# main.net
KiCad netlist of a schematic drawn in Altium Designer
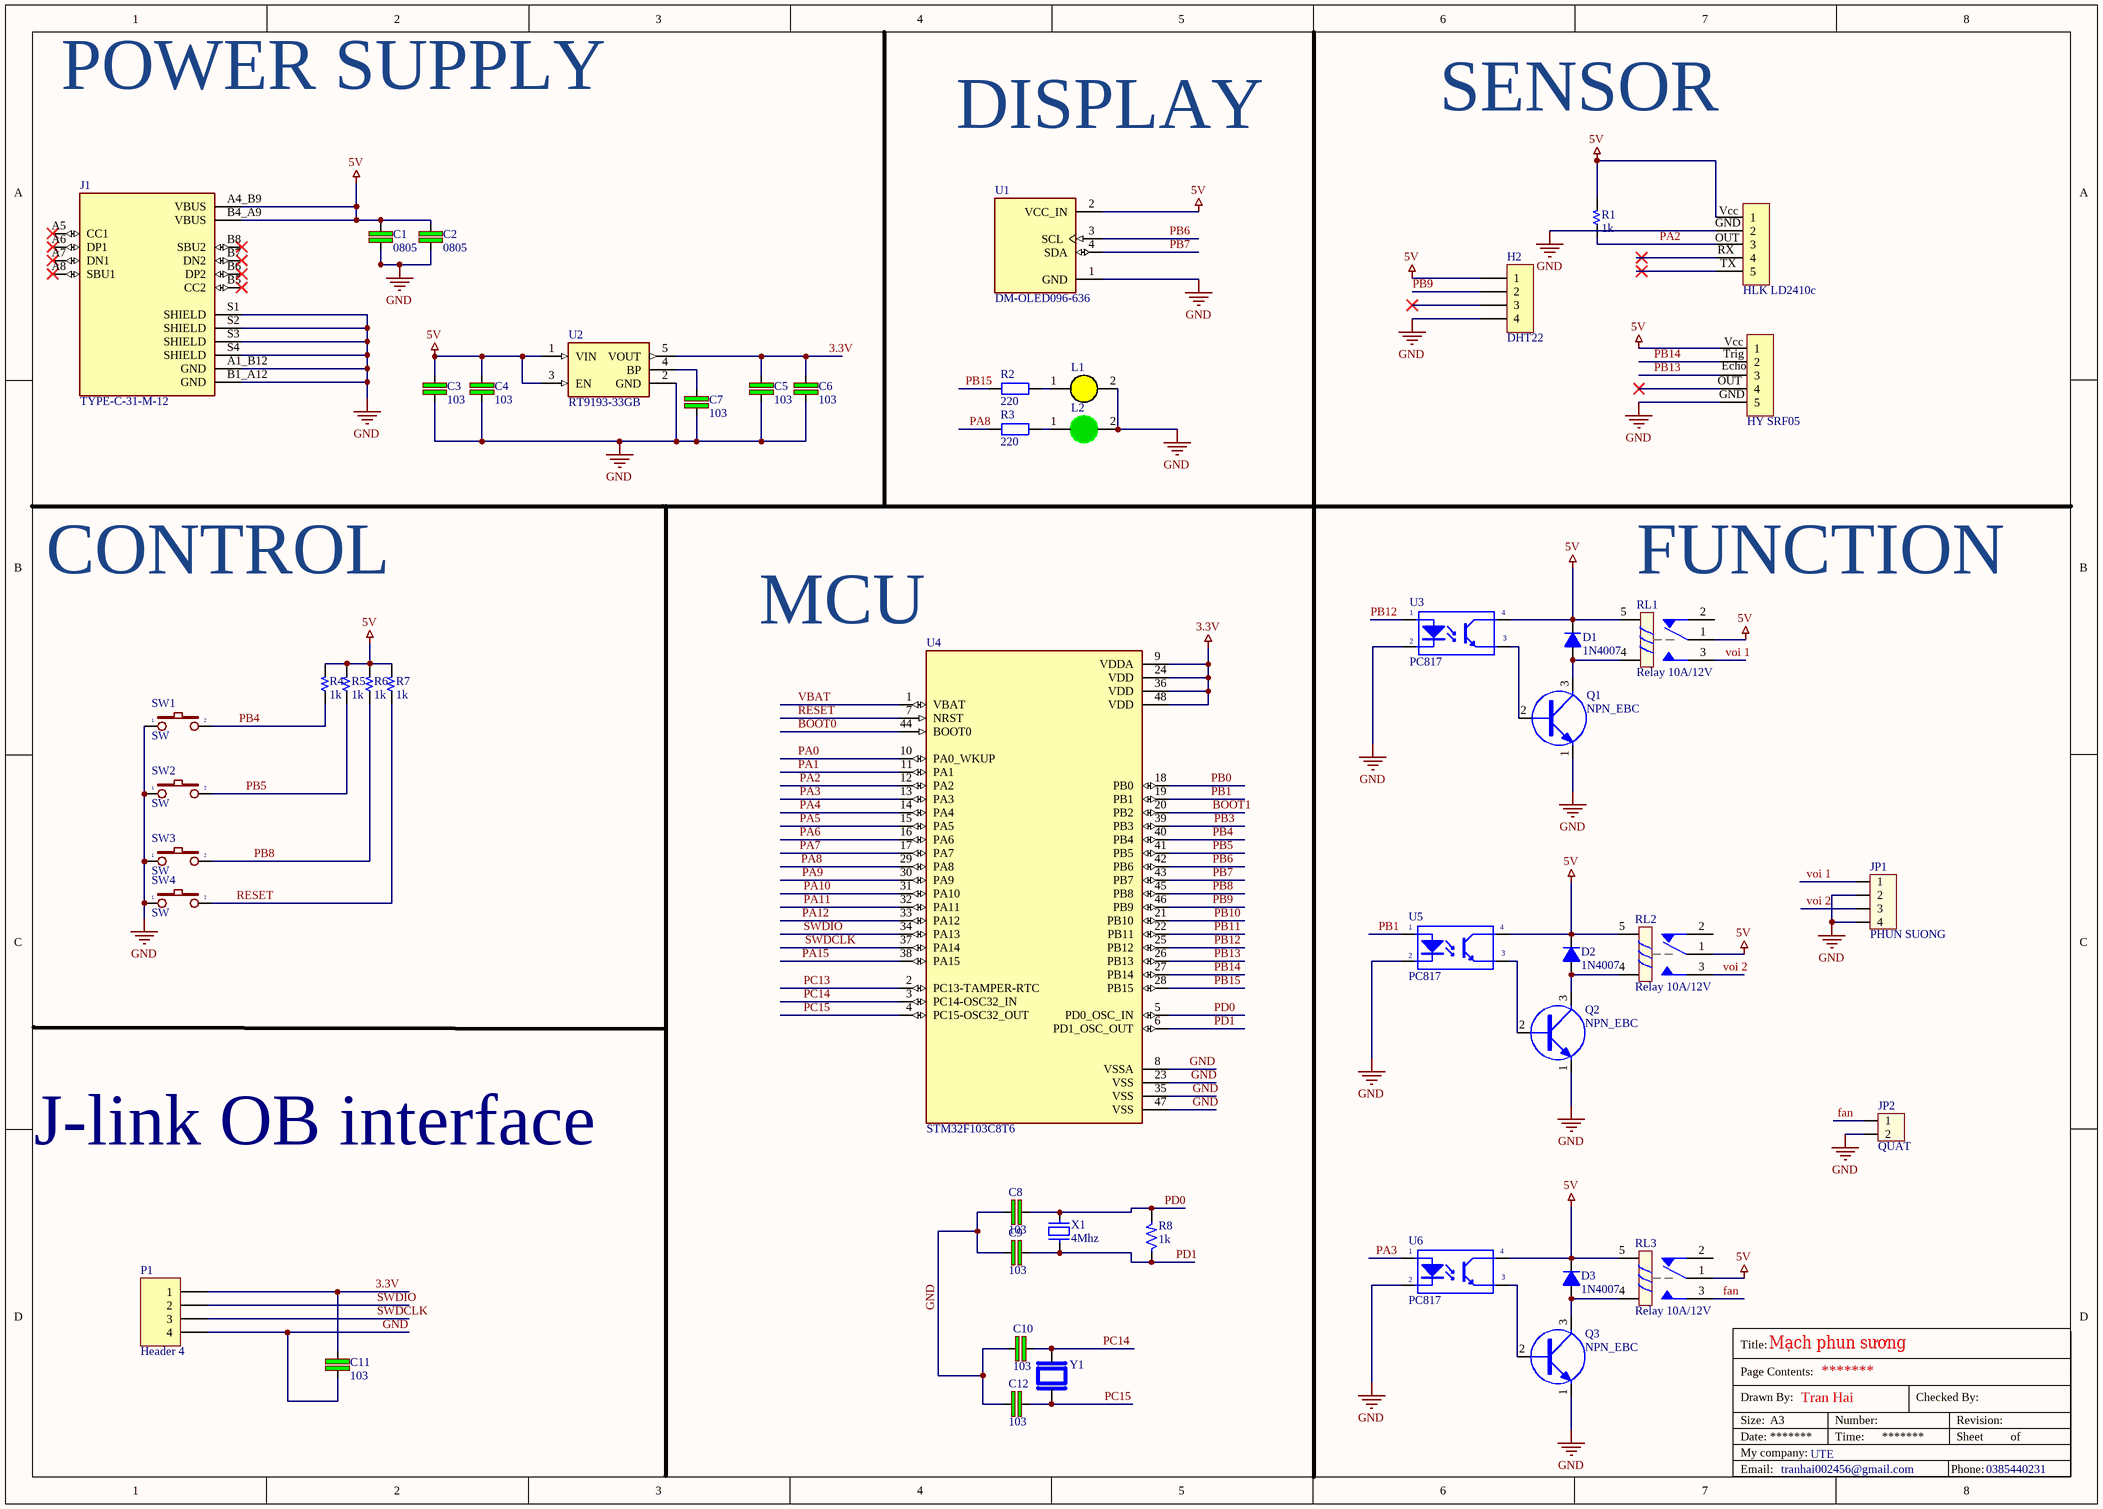
[diagram p0: main.SchDoc]

(export (version "E")
  (design (tool "Eeschema 10.0.6"))
  (components
    (comp (ref "C1")
      (value "0805")
      (footprint "C-0805")
      (description "Cap SMD")
      (libsource (lib "Library AL") (part "C"))
    )
    (comp (ref "C2")
      (value "0805")
      (footprint "C-0805")
      (description "Cap SMD")
      (libsource (lib "Library AL") (part "C"))
    )
    (comp (ref "C3")
      (value "103")
      (footprint "C-0805")
      (description "Cap SMD")
      (libsource (lib "Library AL") (part "C"))
    )
    (comp (ref "C4")
      (value "103")
      (footprint "C-0805")
      (description "Cap SMD")
      (libsource (lib "Library AL") (part "C"))
    )
    (comp (ref "C5")
      (value "103")
      (footprint "C-0805")
      (description "Cap SMD")
      (libsource (lib "Library AL") (part "C"))
    )
    (comp (ref "C6")
      (value "103")
      (footprint "C-0805")
      (description "Cap SMD")
      (libsource (lib "Library AL") (part "C"))
    )
    (comp (ref "C7")
      (value "103")
      (footprint "C-0805")
      (description "Cap SMD")
      (libsource (lib "Library AL") (part "C"))
    )
    (comp (ref "C8")
      (value "103")
      (footprint "C-0805")
      (description "Cap SMD")
      (libsource (lib "") (part "C_1"))
    )
    (comp (ref "C9")
      (value "103")
      (footprint "C-0805")
      (description "Cap SMD")
      (libsource (lib "") (part "C_1"))
    )
    (comp (ref "C10")
      (value "103")
      (footprint "C-0805")
      (description "Cap SMD")
      (libsource (lib "") (part "C_1"))
    )
    (comp (ref "C11")
      (value "103")
      (footprint "C-0805")
      (description "Cap SMD")
      (libsource (lib "Library AL") (part "C"))
    )
    (comp (ref "C12")
      (value "103")
      (footprint "C-0805")
      (description "Cap SMD")
      (libsource (lib "") (part "C_1"))
    )
    (comp (ref "D1")
      (value "1N4007")
      (footprint "D1A")
      (description "Diode 1A")
      (libsource (lib "Library AL") (part "D1A"))
    )
    (comp (ref "D2")
      (value "1N4007")
      (footprint "D1A")
      (description "Diode 1A")
      (libsource (lib "Library AL") (part "D1A"))
    )
    (comp (ref "D3")
      (value "1N4007")
      (footprint "D1A")
      (description "Diode 1A")
      (libsource (lib "Library AL") (part "D1A"))
    )
    (comp (ref "H1")
      (value "HLK LD2410c")
      (footprint "Header 5P DC 2.54")
      (description "Cắm")
      (libsource (lib "Altium_Lib_by_KhueNguyenCreator") (part "Header 5P 2.54 Duc Cong"))
    )
    (comp (ref "H2")
      (value "DHT22")
      (footprint "XH2.54M-4")
      (description "Cắm")
      (libsource (lib "Altium_Lib_by_KhueNguyenCreator") (part "Header 4P 2.54 Duc Thang"))
    )
    (comp (ref "H3")
      (value "HY SRF05")
      (footprint "XH2.54M-5")
      (description "Cắm")
      (libsource (lib "Altium_Lib_by_KhueNguyenCreator") (part "Header 5P 2.54 Duc Thang"))
    )
    (comp (ref "J1")
      (value "TYPE-C-31-M-12")
      (footprint "HRO_TYPE-C-31-M-12")
      (description "USB Connectors 24 Receptacle 1 8.94*7.3mm RoHS")
      (fields (field (name "MF") "HRO Electronics Co., Ltd."))
      (libsource (lib "TYPE-C-31-M-12") (part "TYPE-C-31-M-12"))
    )
    (comp (ref "JP1")
      (value "PHUN SUONG")
      (footprint "CON4")
      (description "Connector 4")
      (libsource (lib "Library AL") (part "Con4"))
    )
    (comp (ref "JP2")
      (value "QUAT")
      (footprint "CON2")
      (description "Connector 2")
      (libsource (lib "Library AL") (part "Con2"))
    )
    (comp (ref "L1")
      (value "LED 0805")
      (footprint "LED-0805-Yellow")
      (description "Dán")
      (libsource (lib "Altium_Lib_by_KhueNguyenCreator") (part "LED 0805 Vang"))
    )
    (comp (ref "L2")
      (value "LED 0805")
      (footprint "LED-0805-Green")
      (description "Dán")
      (libsource (lib "Altium_Lib_by_KhueNguyenCreator") (part "LED 0805 Xanh La"))
    )
    (comp (ref "P1")
      (value "Header 4")
      (footprint "HDR1X4")
      (description "Header, 4-Pin")
      (fields (field (name "PUBLISHER") "Altium Limited"))
      (libsource (lib "Library AL") (part "Header 4"))
    )
    (comp (ref "Q1")
      (value "NPN_EBC")
      (footprint "QTO-92")
      (description "NPN Transistor")
      (libsource (lib "Library AL") (part "NPN_EBC"))
    )
    (comp (ref "Q2")
      (value "NPN_EBC")
      (footprint "QTO-92")
      (description "NPN Transistor")
      (libsource (lib "Library AL") (part "NPN_EBC"))
    )
    (comp (ref "Q3")
      (value "NPN_EBC")
      (footprint "QTO-92")
      (description "NPN Transistor")
      (libsource (lib "Library AL") (part "NPN_EBC"))
    )
    (comp (ref "R1")
      (value "1k")
      (footprint "TRO SMD 0603")
      (libsource (lib "Altium_Lib_by_KhueNguyenCreator") (part "Res_0603"))
    )
    (comp (ref "R2")
      (value "220")
      (footprint "tro smd 0603")
      (description "Dán")
      (libsource (lib "Altium_Lib_by_KhueNguyenCreator") (part "Tro 0603 1% 0R"))
    )
    (comp (ref "R3")
      (value "220")
      (footprint "tro smd 0603")
      (description "Dán")
      (libsource (lib "Altium_Lib_by_KhueNguyenCreator") (part "Tro 0603 1% 0R"))
    )
    (comp (ref "R4")
      (value "1k")
      (footprint "TRO SMD 0603")
      (libsource (lib "Altium_Lib_by_KhueNguyenCreator") (part "Res_0603"))
    )
    (comp (ref "R5")
      (value "1k")
      (footprint "TRO SMD 0603")
      (libsource (lib "Altium_Lib_by_KhueNguyenCreator") (part "Res_0603"))
    )
    (comp (ref "R6")
      (value "1k")
      (footprint "TRO SMD 0603")
      (libsource (lib "Altium_Lib_by_KhueNguyenCreator") (part "Res_0603"))
    )
    (comp (ref "R7")
      (value "1k")
      (footprint "TRO SMD 0603")
      (libsource (lib "Altium_Lib_by_KhueNguyenCreator") (part "Res_0603"))
    )
    (comp (ref "R8")
      (value "1k")
      (footprint "SM-1206")
      (description "Resistor 1/4W")
      (libsource (lib "Library AL") (part "R"))
    )
    (comp (ref "RL1")
      (value "Relay 10A/12V")
      (footprint "RL_SPDT_10A")
      (description "Relay SPDT,10A - 12VDC 5 Pin")
      (libsource (lib "syhaunguyen") (part "Relay 1"))
    )
    (comp (ref "RL2")
      (value "Relay 10A/12V")
      (footprint "RL_SPDT_10A")
      (description "Relay SPDT,10A - 12VDC 5 Pin")
      (libsource (lib "syhaunguyen") (part "Relay 1"))
    )
    (comp (ref "RL3")
      (value "Relay 10A/12V")
      (footprint "RL_SPDT_10A")
      (description "Relay SPDT,10A - 12VDC 5 Pin")
      (libsource (lib "syhaunguyen") (part "Relay 1"))
    )
    (comp (ref "SW1")
      (value "SW")
      (footprint "SW2")
      (description "Switch button 2 pin")
      (libsource (lib "Library AL") (part "SW2"))
    )
    (comp (ref "SW2")
      (value "SW")
      (footprint "SW2")
      (description "Switch button 2 pin")
      (libsource (lib "Library AL") (part "SW2"))
    )
    (comp (ref "SW3")
      (value "SW")
      (footprint "SW2")
      (description "Switch button 2 pin")
      (libsource (lib "Library AL") (part "SW2"))
    )
    (comp (ref "SW4")
      (value "SW")
      (footprint "SW2")
      (description "Switch button 2 pin")
      (libsource (lib "Library AL") (part "SW2"))
    )
    (comp (ref "U1")
      (value "DM-OLED096-636")
      (footprint "MODULE_DM-OLED096-636")
      (description "0.96â€ 128 X 64 MONOCHROME GRAPHIC OLED DISPLAY MODULE - I2C")
      (fields (field (name "MF") "Display Module"))
      (libsource (lib "DM-OLED096-636") (part "DM-OLED096-636"))
    )
    (comp (ref "U2")
      (value "RT9193-33GB")
      (footprint "SOT94P279X129-5N")
      (description "Linear Voltage Regulator IC Positive Fixed 1 Output 300mA TSOT-23-5")
      (fields (field (name "MF") "Richtek USA") (field (name "DIGI-KEY_PART_NUMBER") "1028-1014-2-ND"))
      (libsource (lib "RT9193-33GB") (part "RT9193-33GB"))
    )
    (comp (ref "U3")
      (value "PC817")
      (footprint "DIP4/W0.3")
      (description "Single Opto")
      (libsource (lib "syhaunguyen") (part "PC817"))
    )
    (comp (ref "U4")
      (value "STM32F103C8T6")
      (footprint "QFP50P900X900X160-48N")
      (description "ARM® Cortex®-M3 STM32F1 Microcontroller IC 32-Bit 72MHz 64KB (64K x 8) FLASH 48-LQFP (7x7)")
      (fields (field (name "MF") "STMicroelectronics"))
      (libsource (lib "STM32F103C8T6") (part "STM32F103C8T6"))
    )
    (comp (ref "U5")
      (value "PC817")
      (footprint "DIP4/W0.3")
      (description "Single Opto")
      (libsource (lib "syhaunguyen") (part "PC817"))
    )
    (comp (ref "U6")
      (value "PC817")
      (footprint "DIP4/W0.3")
      (description "Single Opto")
      (libsource (lib "syhaunguyen") (part "PC817"))
    )
    (comp (ref "X1")
      (value "4Mhz")
      (footprint "XT2")
      (description "Crystal For all Crystal 2pin.")
      (libsource (lib "syhaunguyen") (part "XT2"))
    )
    (comp (ref "Y1")
      (value "ABS07-32.768KHZ-T")
      (footprint "XTAL_ABS07-32.768KHZ-T")
      (description "32.768 kHz Â±20ppm Crystal 12.5pF 70 kOhms 2-SMD, No Lead")
      (fields (field (name "MF") "Abracon"))
      (libsource (lib "ABS07-32.768KHZ-T") (part "ABS07-32.768KHZ-T"))
    )
  )
  (nets
    (net (code "1") (name "/BOOT0") (class "Default")
      (node (ref "U4") (pin "44") (pinfunction "BOOT0_44") (pintype "input"))
    )
    (net (code "2") (name "/BOOT1") (class "Default")
      (node (ref "U4") (pin "20") (pinfunction "PB2_20") (pintype "bidirectional"))
    )
    (net (code "3") (name "/PA0") (class "Default")
      (node (ref "U4") (pin "10") (pinfunction "PA0_WKUP_10") (pintype "bidirectional"))
    )
    (net (code "4") (name "/PA1") (class "Default")
      (node (ref "U4") (pin "11") (pinfunction "PA1_11") (pintype "bidirectional"))
    )
    (net (code "5") (name "/PA2") (class "Default")
      (node (ref "H1") (pin "3") (pinfunction "3_3") (pintype "passive"))
      (node (ref "R1") (pin "1") (pinfunction "1_1") (pintype "passive"))
      (node (ref "U4") (pin "12") (pinfunction "PA2_12") (pintype "bidirectional"))
    )
    (net (code "6") (name "/PA3") (class "Default")
      (node (ref "U4") (pin "13") (pinfunction "PA3_13") (pintype "bidirectional"))
      (node (ref "U6") (pin "1") (pinfunction "A_1") (pintype "passive"))
    )
    (net (code "7") (name "/PA4") (class "Default")
      (node (ref "U4") (pin "14") (pinfunction "PA4_14") (pintype "bidirectional"))
    )
    (net (code "8") (name "/PA5") (class "Default")
      (node (ref "U4") (pin "15") (pinfunction "PA5_15") (pintype "bidirectional"))
    )
    (net (code "9") (name "/PA6") (class "Default")
      (node (ref "U4") (pin "16") (pinfunction "PA6_16") (pintype "bidirectional"))
    )
    (net (code "10") (name "/PA7") (class "Default")
      (node (ref "U4") (pin "17") (pinfunction "PA7_17") (pintype "bidirectional"))
    )
    (net (code "11") (name "/PA8") (class "Default")
      (node (ref "R3") (pin "1") (pinfunction "1_1") (pintype "passive"))
      (node (ref "U4") (pin "29") (pinfunction "PA8_29") (pintype "bidirectional"))
    )
    (net (code "12") (name "/PA9") (class "Default")
      (node (ref "U4") (pin "30") (pinfunction "PA9_30") (pintype "bidirectional"))
    )
    (net (code "13") (name "/PA10") (class "Default")
      (node (ref "U4") (pin "31") (pinfunction "PA10_31") (pintype "bidirectional"))
    )
    (net (code "14") (name "/PA11") (class "Default")
      (node (ref "U4") (pin "32") (pinfunction "PA11_32") (pintype "bidirectional"))
    )
    (net (code "15") (name "/PA12") (class "Default")
      (node (ref "U4") (pin "33") (pinfunction "PA12_33") (pintype "bidirectional"))
    )
    (net (code "16") (name "/PA15") (class "Default")
      (node (ref "U4") (pin "38") (pinfunction "PA15_38") (pintype "bidirectional"))
    )
    (net (code "17") (name "/PB0") (class "Default")
      (node (ref "U4") (pin "18") (pinfunction "PB0_18") (pintype "bidirectional"))
    )
    (net (code "18") (name "/PB1") (class "Default")
      (node (ref "U4") (pin "19") (pinfunction "PB1_19") (pintype "bidirectional"))
      (node (ref "U5") (pin "1") (pinfunction "A_1") (pintype "passive"))
    )
    (net (code "19") (name "/PB3") (class "Default")
      (node (ref "U4") (pin "39") (pinfunction "PB3_39") (pintype "bidirectional"))
    )
    (net (code "20") (name "/PB4") (class "Default")
      (node (ref "R4") (pin "1") (pinfunction "1_1") (pintype "passive"))
      (node (ref "SW1") (pin "2") (pinfunction "2_2") (pintype "passive"))
      (node (ref "U4") (pin "40") (pinfunction "PB4_40") (pintype "bidirectional"))
    )
    (net (code "21") (name "/PB5") (class "Default")
      (node (ref "R5") (pin "1") (pinfunction "1_1") (pintype "passive"))
      (node (ref "SW2") (pin "2") (pinfunction "2_2") (pintype "passive"))
      (node (ref "U4") (pin "41") (pinfunction "PB5_41") (pintype "bidirectional"))
    )
    (net (code "22") (name "/PB6") (class "Default")
      (node (ref "U1") (pin "3") (pinfunction "SCL_3") (pintype "input"))
      (node (ref "U4") (pin "42") (pinfunction "PB6_42") (pintype "bidirectional"))
    )
    (net (code "23") (name "/PB7") (class "Default")
      (node (ref "U1") (pin "4") (pinfunction "SDA_4") (pintype "bidirectional"))
      (node (ref "U4") (pin "43") (pinfunction "PB7_43") (pintype "bidirectional"))
    )
    (net (code "24") (name "/PB8") (class "Default")
      (node (ref "R6") (pin "1") (pinfunction "1_1") (pintype "passive"))
      (node (ref "SW3") (pin "2") (pinfunction "2_2") (pintype "passive"))
      (node (ref "U4") (pin "45") (pinfunction "PB8_45") (pintype "bidirectional"))
    )
    (net (code "25") (name "/PB9") (class "Default")
      (node (ref "H2") (pin "2") (pinfunction "2_2") (pintype "passive"))
      (node (ref "U4") (pin "46") (pinfunction "PB9_46") (pintype "bidirectional"))
    )
    (net (code "26") (name "/PB10") (class "Default")
      (node (ref "U4") (pin "21") (pinfunction "PB10_21") (pintype "bidirectional"))
    )
    (net (code "27") (name "/PB11") (class "Default")
      (node (ref "U4") (pin "22") (pinfunction "PB11_22") (pintype "bidirectional"))
    )
    (net (code "28") (name "/PB12") (class "Default")
      (node (ref "U3") (pin "1") (pinfunction "A_1") (pintype "passive"))
      (node (ref "U4") (pin "25") (pinfunction "PB12_25") (pintype "bidirectional"))
    )
    (net (code "29") (name "/PB13") (class "Default")
      (node (ref "H3") (pin "3") (pinfunction "3_3") (pintype "passive"))
      (node (ref "U4") (pin "26") (pinfunction "PB13_26") (pintype "bidirectional"))
    )
    (net (code "30") (name "/PB14") (class "Default")
      (node (ref "H3") (pin "2") (pinfunction "2_2") (pintype "passive"))
      (node (ref "U4") (pin "27") (pinfunction "PB14_27") (pintype "bidirectional"))
    )
    (net (code "31") (name "/PB15") (class "Default")
      (node (ref "R2") (pin "1") (pinfunction "1_1") (pintype "passive"))
      (node (ref "U4") (pin "28") (pinfunction "PB15_28") (pintype "bidirectional"))
    )
    (net (code "32") (name "/PC13") (class "Default")
      (node (ref "U4") (pin "2") (pinfunction "PC13-TAMPER-RTC_2") (pintype "bidirectional"))
    )
    (net (code "33") (name "/PC14") (class "Default")
      (node (ref "C10") (pin "2") (pinfunction "2_2") (pintype "passive"))
      (node (ref "U4") (pin "3") (pinfunction "PC14-OSC32_IN_3") (pintype "bidirectional"))
      (node (ref "Y1") (pin "2") (pinfunction "2_2") (pintype "passive"))
    )
    (net (code "34") (name "/PC15") (class "Default")
      (node (ref "C12") (pin "2") (pinfunction "2_2") (pintype "passive"))
      (node (ref "U4") (pin "4") (pinfunction "PC15-OSC32_OUT_4") (pintype "bidirectional"))
      (node (ref "Y1") (pin "1") (pinfunction "1_1") (pintype "passive"))
    )
    (net (code "35") (name "/PD0") (class "Default")
      (node (ref "C8") (pin "2") (pinfunction "2_2") (pintype "passive"))
      (node (ref "R8") (pin "2") (pinfunction "2_2") (pintype "passive"))
      (node (ref "U4") (pin "5") (pinfunction "PD0_OSC_IN_5") (pintype "bidirectional"))
      (node (ref "X1") (pin "1") (pinfunction "1_1") (pintype "passive"))
    )
    (net (code "36") (name "/PD1") (class "Default")
      (node (ref "C9") (pin "2") (pinfunction "2_2") (pintype "passive"))
      (node (ref "R8") (pin "1") (pinfunction "1_1") (pintype "passive"))
      (node (ref "U4") (pin "6") (pinfunction "PD1_OSC_OUT_6") (pintype "bidirectional"))
      (node (ref "X1") (pin "2") (pinfunction "2_2") (pintype "passive"))
    )
    (net (code "37") (name "/RESET") (class "Default")
      (node (ref "R7") (pin "1") (pinfunction "1_1") (pintype "passive"))
      (node (ref "SW4") (pin "2") (pinfunction "2_2") (pintype "passive"))
      (node (ref "U4") (pin "7") (pinfunction "NRST_7") (pintype "input"))
    )
    (net (code "38") (name "/SWDCLK") (class "Default")
      (node (ref "P1") (pin "3") (pinfunction "3_3") (pintype "passive"))
      (node (ref "U4") (pin "37") (pinfunction "PA14_37") (pintype "bidirectional"))
    )
    (net (code "39") (name "/SWDIO") (class "Default")
      (node (ref "P1") (pin "2") (pinfunction "2_2") (pintype "passive"))
      (node (ref "U4") (pin "34") (pinfunction "PA13_34") (pintype "bidirectional"))
    )
    (net (code "40") (name "/VBAT") (class "Default")
      (node (ref "U4") (pin "1") (pinfunction "VBAT_1") (pintype "bidirectional"))
    )
    (net (code "41") (name "/fan") (class "Default")
      (node (ref "JP2") (pin "1") (pinfunction "1_1") (pintype "passive"))
      (node (ref "RL3") (pin "3") (pinfunction "3_3") (pintype "passive"))
    )
    (net (code "42") (name "/voi 1") (class "Default")
      (node (ref "JP1") (pin "1") (pinfunction "1_1") (pintype "passive"))
      (node (ref "RL1") (pin "3") (pinfunction "3_3") (pintype "passive"))
    )
    (net (code "43") (name "/voi 2") (class "Default")
      (node (ref "JP1") (pin "3") (pinfunction "3_3") (pintype "passive"))
      (node (ref "RL2") (pin "3") (pinfunction "3_3") (pintype "passive"))
    )
    (net (code "44") (name "3.3V") (class "Default")
      (node (ref "C11") (pin "2") (pinfunction "2_2") (pintype "passive"))
      (node (ref "C5") (pin "2") (pinfunction "2_2") (pintype "passive"))
      (node (ref "C6") (pin "2") (pinfunction "2_2") (pintype "passive"))
      (node (ref "P1") (pin "1") (pinfunction "1_1") (pintype "passive"))
      (node (ref "U2") (pin "5") (pinfunction "VOUT_5") (pintype "output"))
      (node (ref "U4") (pin "24") (pinfunction "VDD_24") (pintype "power_in"))
      (node (ref "U4") (pin "36") (pinfunction "VDD_36") (pintype "power_in"))
      (node (ref "U4") (pin "48") (pinfunction "VDD_48") (pintype "power_in"))
      (node (ref "U4") (pin "9") (pinfunction "VDDA_9") (pintype "power_in"))
    )
    (net (code "45") (name "5V") (class "Default")
      (node (ref "C1") (pin "2") (pinfunction "2_2") (pintype "passive"))
      (node (ref "C2") (pin "2") (pinfunction "2_2") (pintype "passive"))
      (node (ref "C3") (pin "2") (pinfunction "2_2") (pintype "passive"))
      (node (ref "C4") (pin "2") (pinfunction "2_2") (pintype "passive"))
      (node (ref "D1") (pin "2") (pinfunction "K_2") (pintype "passive"))
      (node (ref "D2") (pin "2") (pinfunction "K_2") (pintype "passive"))
      (node (ref "D3") (pin "2") (pinfunction "K_2") (pintype "passive"))
      (node (ref "H1") (pin "1") (pinfunction "1_1") (pintype "passive"))
      (node (ref "H2") (pin "1") (pinfunction "1_1") (pintype "passive"))
      (node (ref "H3") (pin "1") (pinfunction "1_1") (pintype "passive"))
      (node (ref "J1") (pin "A4_B9") (pinfunction "VBUS_A4_B9") (pintype "power_in"))
      (node (ref "J1") (pin "B4_A9") (pinfunction "VBUS_B4_A9") (pintype "power_in"))
      (node (ref "R1") (pin "2") (pinfunction "2_2") (pintype "passive"))
      (node (ref "R4") (pin "2") (pinfunction "2_2") (pintype "passive"))
      (node (ref "R5") (pin "2") (pinfunction "2_2") (pintype "passive"))
      (node (ref "R6") (pin "2") (pinfunction "2_2") (pintype "passive"))
      (node (ref "R7") (pin "2") (pinfunction "2_2") (pintype "passive"))
      (node (ref "RL1") (pin "1") (pinfunction "1_1") (pintype "passive"))
      (node (ref "RL1") (pin "5") (pinfunction "5_5") (pintype "passive"))
      (node (ref "RL2") (pin "1") (pinfunction "1_1") (pintype "passive"))
      (node (ref "RL2") (pin "5") (pinfunction "5_5") (pintype "passive"))
      (node (ref "RL3") (pin "1") (pinfunction "1_1") (pintype "passive"))
      (node (ref "RL3") (pin "5") (pinfunction "5_5") (pintype "passive"))
      (node (ref "U1") (pin "2") (pinfunction "VCC_IN_2") (pintype "power_in"))
      (node (ref "U2") (pin "1") (pinfunction "VIN_1") (pintype "input"))
      (node (ref "U2") (pin "3") (pinfunction "EN_3") (pintype "input"))
      (node (ref "U3") (pin "4") (pinfunction "C_4") (pintype "passive"))
      (node (ref "U5") (pin "4") (pinfunction "C_4") (pintype "passive"))
      (node (ref "U6") (pin "4") (pinfunction "C_4") (pintype "passive"))
    )
    (net (code "46") (name "GND") (class "Default")
      (node (ref "C1") (pin "1") (pinfunction "1_1") (pintype "passive"))
      (node (ref "C10") (pin "1") (pinfunction "1_1") (pintype "passive"))
      (node (ref "C11") (pin "1") (pinfunction "1_1") (pintype "passive"))
      (node (ref "C12") (pin "1") (pinfunction "1_1") (pintype "passive"))
      (node (ref "C2") (pin "1") (pinfunction "1_1") (pintype "passive"))
      (node (ref "C3") (pin "1") (pinfunction "1_1") (pintype "passive"))
      (node (ref "C4") (pin "1") (pinfunction "1_1") (pintype "passive"))
      (node (ref "C5") (pin "1") (pinfunction "1_1") (pintype "passive"))
      (node (ref "C6") (pin "1") (pinfunction "1_1") (pintype "passive"))
      (node (ref "C7") (pin "1") (pinfunction "1_1") (pintype "passive"))
      (node (ref "C8") (pin "1") (pinfunction "1_1") (pintype "passive"))
      (node (ref "C9") (pin "1") (pinfunction "1_1") (pintype "passive"))
      (node (ref "H1") (pin "2") (pinfunction "2_2") (pintype "passive"))
      (node (ref "H2") (pin "4") (pinfunction "4_4") (pintype "passive"))
      (node (ref "H3") (pin "5") (pinfunction "5_5") (pintype "passive"))
      (node (ref "J1") (pin "A1_B12") (pinfunction "GND_A1_B12") (pintype "power_in"))
      (node (ref "J1") (pin "B1_A12") (pinfunction "GND_B1_A12") (pintype "power_in"))
      (node (ref "J1") (pin "S1") (pinfunction "SHIELD_S1") (pintype "passive"))
      (node (ref "J1") (pin "S2") (pinfunction "SHIELD_S2") (pintype "passive"))
      (node (ref "J1") (pin "S3") (pinfunction "SHIELD_S3") (pintype "passive"))
      (node (ref "J1") (pin "S4") (pinfunction "SHIELD_S4") (pintype "passive"))
      (node (ref "JP1") (pin "2") (pinfunction "2_2") (pintype "passive"))
      (node (ref "JP1") (pin "4") (pinfunction "4_4") (pintype "passive"))
      (node (ref "JP2") (pin "2") (pinfunction "2_2") (pintype "passive"))
      (node (ref "L1") (pin "2") (pinfunction "K_2") (pintype "passive"))
      (node (ref "L2") (pin "2") (pinfunction "K_2") (pintype "passive"))
      (node (ref "P1") (pin "4") (pinfunction "4_4") (pintype "passive"))
      (node (ref "Q1") (pin "1") (pinfunction "E_1") (pintype "passive"))
      (node (ref "Q2") (pin "1") (pinfunction "E_1") (pintype "passive"))
      (node (ref "Q3") (pin "1") (pinfunction "E_1") (pintype "passive"))
      (node (ref "SW1") (pin "1") (pinfunction "1_1") (pintype "passive"))
      (node (ref "SW2") (pin "1") (pinfunction "1_1") (pintype "passive"))
      (node (ref "SW3") (pin "1") (pinfunction "1_1") (pintype "passive"))
      (node (ref "SW4") (pin "1") (pinfunction "1_1") (pintype "passive"))
      (node (ref "U1") (pin "1") (pinfunction "GND_1") (pintype "power_in"))
      (node (ref "U2") (pin "2") (pinfunction "GND_2") (pintype "power_in"))
      (node (ref "U3") (pin "2") (pinfunction "K_2") (pintype "passive"))
      (node (ref "U4") (pin "23") (pinfunction "VSS_23") (pintype "power_in"))
      (node (ref "U4") (pin "35") (pinfunction "VSS_35") (pintype "power_in"))
      (node (ref "U4") (pin "47") (pinfunction "VSS_47") (pintype "power_in"))
      (node (ref "U4") (pin "8") (pinfunction "VSSA_8") (pintype "power_in"))
      (node (ref "U5") (pin "2") (pinfunction "K_2") (pintype "passive"))
      (node (ref "U6") (pin "2") (pinfunction "K_2") (pintype "passive"))
    )
    (net (code "47") (name "Net-(D1-A)") (class "Default")
      (node (ref "D1") (pin "1") (pinfunction "A_1") (pintype "passive"))
      (node (ref "Q1") (pin "3") (pinfunction "C_3") (pintype "passive"))
      (node (ref "RL1") (pin "4") (pinfunction "4_4") (pintype "passive"))
    )
    (net (code "48") (name "Net-(D2-A)") (class "Default")
      (node (ref "D2") (pin "1") (pinfunction "A_1") (pintype "passive"))
      (node (ref "Q2") (pin "3") (pinfunction "C_3") (pintype "passive"))
      (node (ref "RL2") (pin "4") (pinfunction "4_4") (pintype "passive"))
    )
    (net (code "49") (name "Net-(D3-A)") (class "Default")
      (node (ref "D3") (pin "1") (pinfunction "A_1") (pintype "passive"))
      (node (ref "Q3") (pin "3") (pinfunction "C_3") (pintype "passive"))
      (node (ref "RL3") (pin "4") (pinfunction "4_4") (pintype "passive"))
    )
    (net (code "50") (name "Net-(L1-A)") (class "Default")
      (node (ref "L1") (pin "1") (pinfunction "A_1") (pintype "passive"))
      (node (ref "R2") (pin "2") (pinfunction "2_2") (pintype "passive"))
    )
    (net (code "51") (name "Net-(L2-A)") (class "Default")
      (node (ref "L2") (pin "1") (pinfunction "A_1") (pintype "passive"))
      (node (ref "R3") (pin "2") (pinfunction "2_2") (pintype "passive"))
    )
    (net (code "52") (name "Net-(Q1-B)") (class "Default")
      (node (ref "Q1") (pin "2") (pinfunction "B_2") (pintype "passive"))
      (node (ref "U3") (pin "3") (pinfunction "E_3") (pintype "passive"))
    )
    (net (code "53") (name "Net-(Q2-B)") (class "Default")
      (node (ref "Q2") (pin "2") (pinfunction "B_2") (pintype "passive"))
      (node (ref "U5") (pin "3") (pinfunction "E_3") (pintype "passive"))
    )
    (net (code "54") (name "Net-(Q3-B)") (class "Default")
      (node (ref "Q3") (pin "2") (pinfunction "B_2") (pintype "passive"))
      (node (ref "U6") (pin "3") (pinfunction "E_3") (pintype "passive"))
    )
    (net (code "55") (name "Net-(U2-BP)") (class "Default")
      (node (ref "C7") (pin "2") (pinfunction "2_2") (pintype "passive"))
      (node (ref "U2") (pin "4") (pinfunction "BP_4") (pintype "passive"))
    )
    (net (code "56") (name "unconnected-(H1-Pad4)") (class "Default")
      (node (ref "H1") (pin "4") (pinfunction "4_4") (pintype "passive"))
    )
    (net (code "57") (name "unconnected-(H1-Pad5)") (class "Default")
      (node (ref "H1") (pin "5") (pinfunction "5_5") (pintype "passive"))
    )
    (net (code "58") (name "unconnected-(H2-Pad3)") (class "Default")
      (node (ref "H2") (pin "3") (pinfunction "3_3") (pintype "passive+no_connect"))
    )
    (net (code "59") (name "unconnected-(H3-Pad4)") (class "Default")
      (node (ref "H3") (pin "4") (pinfunction "4_4") (pintype "passive+no_connect"))
    )
    (net (code "60") (name "unconnected-(J1-CC1-PadA5)") (class "Default")
      (node (ref "J1") (pin "A5") (pinfunction "CC1_A5") (pintype "bidirectional+no_connect"))
    )
    (net (code "61") (name "unconnected-(J1-CC2-PadB5)") (class "Default")
      (node (ref "J1") (pin "B5") (pinfunction "CC2_B5") (pintype "bidirectional+no_connect"))
    )
    (net (code "62") (name "unconnected-(J1-DN1-PadA7)") (class "Default")
      (node (ref "J1") (pin "A7") (pinfunction "DN1_A7") (pintype "bidirectional+no_connect"))
    )
    (net (code "63") (name "unconnected-(J1-DN2-PadB7)") (class "Default")
      (node (ref "J1") (pin "B7") (pinfunction "DN2_B7") (pintype "bidirectional+no_connect"))
    )
    (net (code "64") (name "unconnected-(J1-DP1-PadA6)") (class "Default")
      (node (ref "J1") (pin "A6") (pinfunction "DP1_A6") (pintype "bidirectional+no_connect"))
    )
    (net (code "65") (name "unconnected-(J1-DP2-PadB6)") (class "Default")
      (node (ref "J1") (pin "B6") (pinfunction "DP2_B6") (pintype "bidirectional+no_connect"))
    )
    (net (code "66") (name "unconnected-(J1-SBU1-PadA8)") (class "Default")
      (node (ref "J1") (pin "A8") (pinfunction "SBU1_A8") (pintype "bidirectional+no_connect"))
    )
    (net (code "67") (name "unconnected-(J1-SBU2-PadB8)") (class "Default")
      (node (ref "J1") (pin "B8") (pinfunction "SBU2_B8") (pintype "bidirectional+no_connect"))
    )
    (net (code "68") (name "unconnected-(RL1-Pad2)") (class "Default")
      (node (ref "RL1") (pin "2") (pinfunction "2_2") (pintype "passive"))
    )
    (net (code "69") (name "unconnected-(RL2-Pad2)") (class "Default")
      (node (ref "RL2") (pin "2") (pinfunction "2_2") (pintype "passive"))
    )
    (net (code "70") (name "unconnected-(RL3-Pad2)") (class "Default")
      (node (ref "RL3") (pin "2") (pinfunction "2_2") (pintype "passive"))
    )
  )
)
